# PWR_REVE_2.net
KiCad netlist of a schematic drawn in Altium Designer
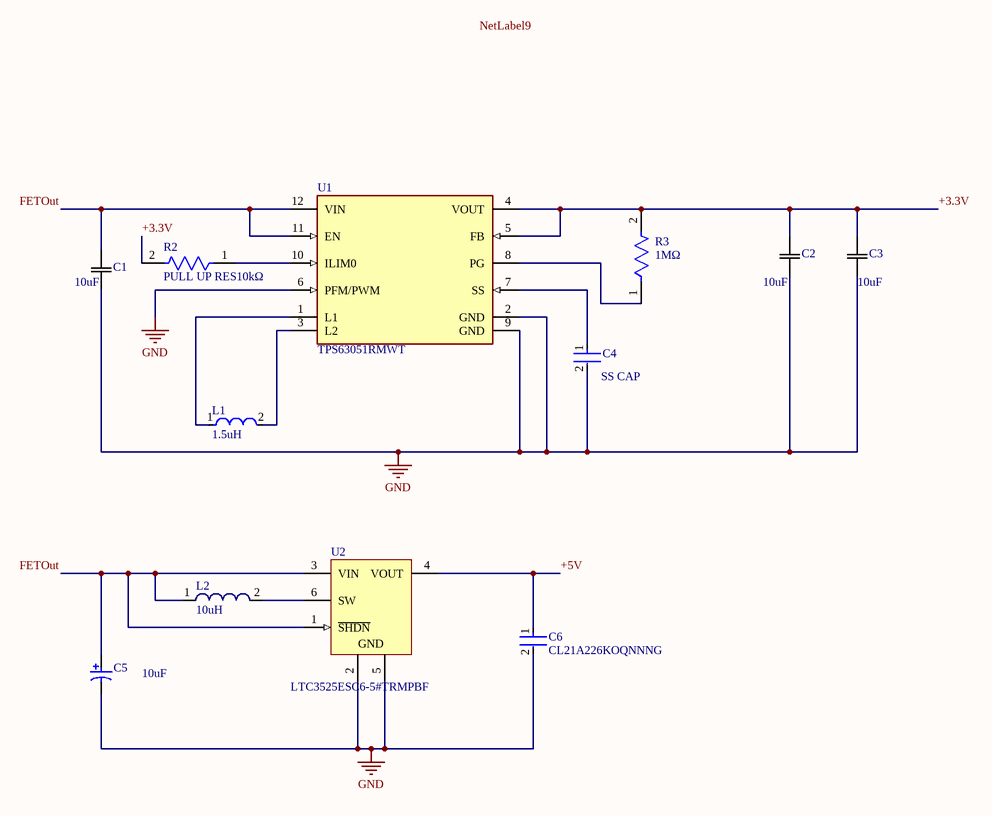
[diagram p0: PWR_REVE_2.SchDoc]

(export (version "E")
  (design (tool "Eeschema 10.0.6"))
  (components
    (comp (ref "C1")
      (value "10uF")
      (footprint "G-188_MUR")
      (description "No Description Available")
      (fields
        (field (name "MANUFACTURER_PART_NUMBER") "GRM188R60J106ME84D")
        (field (name "COPYRIGHT") "Copyright (C) 2022 Ultra Librarian. All rights reserved.")
      )
      (libsource (lib "PWR_REVE") (part "GRM188R60J106ME84D"))
    )
    (comp (ref "C2")
      (value "10uF")
      (footprint "G-188_MUR")
      (description "No Description Available")
      (fields
        (field (name "MANUFACTURER_PART_NUMBER") "GRM188R60J106ME84D")
        (field (name "COPYRIGHT") "Copyright (C) 2022 Ultra Librarian. All rights reserved.")
      )
      (libsource (lib "PWR_REVE") (part "GRM188R60J106ME84D"))
    )
    (comp (ref "C3")
      (value "10uF")
      (footprint "G-188_MUR")
      (description "No Description Available")
      (fields
        (field (name "MANUFACTURER_PART_NUMBER") "GRM188R60J106ME84D")
        (field (name "COPYRIGHT") "Copyright (C) 2022 Ultra Librarian. All rights reserved.")
      )
      (libsource (lib "PWR_REVE") (part "GRM188R60J106ME84D"))
    )
    (comp (ref "C4")
      (value "SS CAP")
      (footprint "FP-CBR08C-MFG")
      (description "CAP0805")
      (fields
        (field (name "OCTOPART") "https://octopart.com/cbr08c470fagac-kemet-23843310")
        (field (name "TOLERANCE") "0.01")
      )
      (libsource (lib "Altium Content Vault") (part "11868f565c42a9108669ba33697ecf6"))
    )
    (comp (ref "C5")
      (value "10uF")
      (footprint "VISH-293D-A_L")
      (description "Tantalum Capacitor, 10 uF, +/- 10%, 10 V, -55 to 125 degC, 1206 (3216 Metric), RoHS, Tape and Reel")
      (fields (field (name "VOLTAGE") "10VDC") (field (name "MANUFACTURER") "Vishay"))
      (libsource (lib "Altium Content Vault") (part "CAP-P-2"))
    )
    (comp (ref "C6")
      (value "CL21A226KOQNNNG")
      (footprint "FP-CL21-IPC_A")
      (description "CL21 Series 0805 22uF 16V ±10% Tolerance X5R Multilayer Ceramic Chip Capacitor")
      (fields (field (name "TOLERANCE") "10%"))
      (libsource (lib "Altium Content Vault") (part "b4654b650e69147ec39a6b967a45e02"))
    )
    (comp (ref "L1")
      (value "1.5uH")
      (footprint "FP-DFE252010C-IPC_C")
      (description "Shielded Wirewound Inductor 1.5uH  1900mA 0.108Ω 1008 (2520)")
      (fields (field (name "TOLERANCE") "20%"))
      (libsource (lib "Altium Content Vault") (part "725321dda6339637d4d059423bc1c3c"))
    )
    (comp (ref "L2")
      (value "10uH")
      (footprint "WE-PD2SR 7850")
      (description "Shielded Power Inductor WE-PD2SR, L=10.0 µH")
      (fields (field (name "MANUFACTURER") "Wuerth Elektronik") (field (name "PARTNUMBER") "744787100"))
      (libsource (lib "Altium Content Vault") (part "WE-IND-INDUCTOR-2"))
    )
    (comp (ref "R2")
      (value "PULL UP RES10kΩ")
      (footprint "FP-RMCF0805-IPC_C")
      (description "10kΩ 0805")
      (fields (field (name "TOLERANCE") "5%"))
      (libsource (lib "Altium Content Vault") (part "1029c3af85768c4190bb7ad29bc67b5"))
    )
    (comp (ref "R3")
      (value "1MΩ")
      (footprint "FP-RMCF0805-IPC_C")
      (description "1MΩ ±5% 0.125W 0805 Thick Film Chip Resistor AEC-Q200 compliant")
      (fields (field (name "TOLERANCE") "5%"))
      (libsource (lib "Altium Content Vault") (part "1029c3af85768c4190bb7ad29bc67b5"))
    )
    (comp (ref "U1")
      (value "TPS63051RMWT")
      (footprint "FP-RMW0012A-IPC_A")
      (description "IC REG BCK BST 3.3V 500MA 12VQFN")
      (libsource (lib "Altium Content Vault") (part "a09332d505cf38b86d9208cc3834c0d"))
    )
    (comp (ref "U2")
      (value "LTC3525ESC6-5#TRMPBF")
      (footprint "LT-SC6-6-SC70_N")
      (fields (field (name "MANUFACTURER") "Linear Technology"))
      (libsource (lib "Altium Content Vault") (part "LT-LTC3525_3525D_3525L"))
    )
  )
  (nets
    (net (code "1") (name "/+3.3V") (class "Default")
      (node (ref "C2") (pin "2") (pinfunction "2_2") (pintype "passive"))
      (node (ref "C3") (pin "2") (pinfunction "2_2") (pintype "passive"))
      (node (ref "R2") (pin "2") (pinfunction "2_2") (pintype "passive"))
      (node (ref "R3") (pin "2") (pinfunction "2_2") (pintype "passive"))
      (node (ref "U1") (pin "4") (pinfunction "VOUT_4") (pintype "power_in"))
      (node (ref "U1") (pin "5") (pinfunction "FB_5") (pintype "input"))
    )
    (net (code "2") (name "/+5V") (class "Default")
      (node (ref "C6") (pin "1") (pinfunction "1_1") (pintype "passive"))
      (node (ref "U2") (pin "4") (pinfunction "VOUT_4") (pintype "power_in"))
    )
    (net (code "3") (name "/FETOut") (class "Default")
      (node (ref "C1") (pin "2") (pinfunction "2_2") (pintype "passive"))
      (node (ref "C5") (pin "1") (pinfunction "1_1") (pintype "passive"))
      (node (ref "L2") (pin "1") (pinfunction "1_1") (pintype "passive"))
      (node (ref "U1") (pin "11") (pinfunction "EN_11") (pintype "input"))
      (node (ref "U1") (pin "12") (pinfunction "VIN_12") (pintype "power_in"))
      (node (ref "U2") (pin "1") (pinfunction "~{SHDN}_1") (pintype "input"))
      (node (ref "U2") (pin "3") (pinfunction "VIN_3") (pintype "power_in"))
    )
    (net (code "5") (name "GND") (class "Default")
      (node (ref "C1") (pin "1") (pinfunction "1_1") (pintype "passive"))
      (node (ref "C2") (pin "1") (pinfunction "1_1") (pintype "passive"))
      (node (ref "C3") (pin "1") (pinfunction "1_1") (pintype "passive"))
      (node (ref "C4") (pin "2") (pinfunction "2_2") (pintype "passive"))
      (node (ref "C5") (pin "2") (pinfunction "2_2") (pintype "passive"))
      (node (ref "C6") (pin "2") (pinfunction "2_2") (pintype "passive"))
      (node (ref "U1") (pin "2") (pinfunction "GND_2") (pintype "power_in"))
      (node (ref "U1") (pin "6") (pinfunction "PFM/PWM_6") (pintype "input"))
      (node (ref "U1") (pin "9") (pinfunction "GND_9") (pintype "power_in"))
      (node (ref "U2") (pin "2") (pinfunction "GND_2") (pintype "power_in"))
      (node (ref "U2") (pin "5") (pinfunction "GND_5") (pintype "power_in"))
    )
    (net (code "6") (name "Net-(U1-ILIM0)") (class "Default")
      (node (ref "R2") (pin "1") (pinfunction "1_1") (pintype "passive"))
      (node (ref "U1") (pin "10") (pinfunction "ILIM0_10") (pintype "input"))
    )
    (net (code "7") (name "Net-(U1-L1)") (class "Default")
      (node (ref "L1") (pin "1") (pinfunction "1_1") (pintype "passive"))
      (node (ref "U1") (pin "1") (pinfunction "L1_1") (pintype "passive"))
    )
    (net (code "8") (name "Net-(U1-L2)") (class "Default")
      (node (ref "L1") (pin "2") (pinfunction "2_2") (pintype "passive"))
      (node (ref "U1") (pin "3") (pinfunction "L2_3") (pintype "passive"))
    )
    (net (code "9") (name "Net-(U1-PG)") (class "Default")
      (node (ref "R3") (pin "1") (pinfunction "1_1") (pintype "passive"))
      (node (ref "U1") (pin "8") (pinfunction "PG_8") (pintype "open_collector"))
    )
    (net (code "10") (name "Net-(U1-SS)") (class "Default")
      (node (ref "C4") (pin "1") (pinfunction "1_1") (pintype "passive"))
      (node (ref "U1") (pin "7") (pinfunction "SS_7") (pintype "input"))
    )
    (net (code "11") (name "Net-(U2-SW)") (class "Default")
      (node (ref "L2") (pin "2") (pinfunction "2_2") (pintype "passive"))
      (node (ref "U2") (pin "6") (pinfunction "SW_6") (pintype "passive"))
    )
  )
)
